# Multi-sensor_Datalogger.net
KiCad netlist of a schematic drawn in Altium Designer
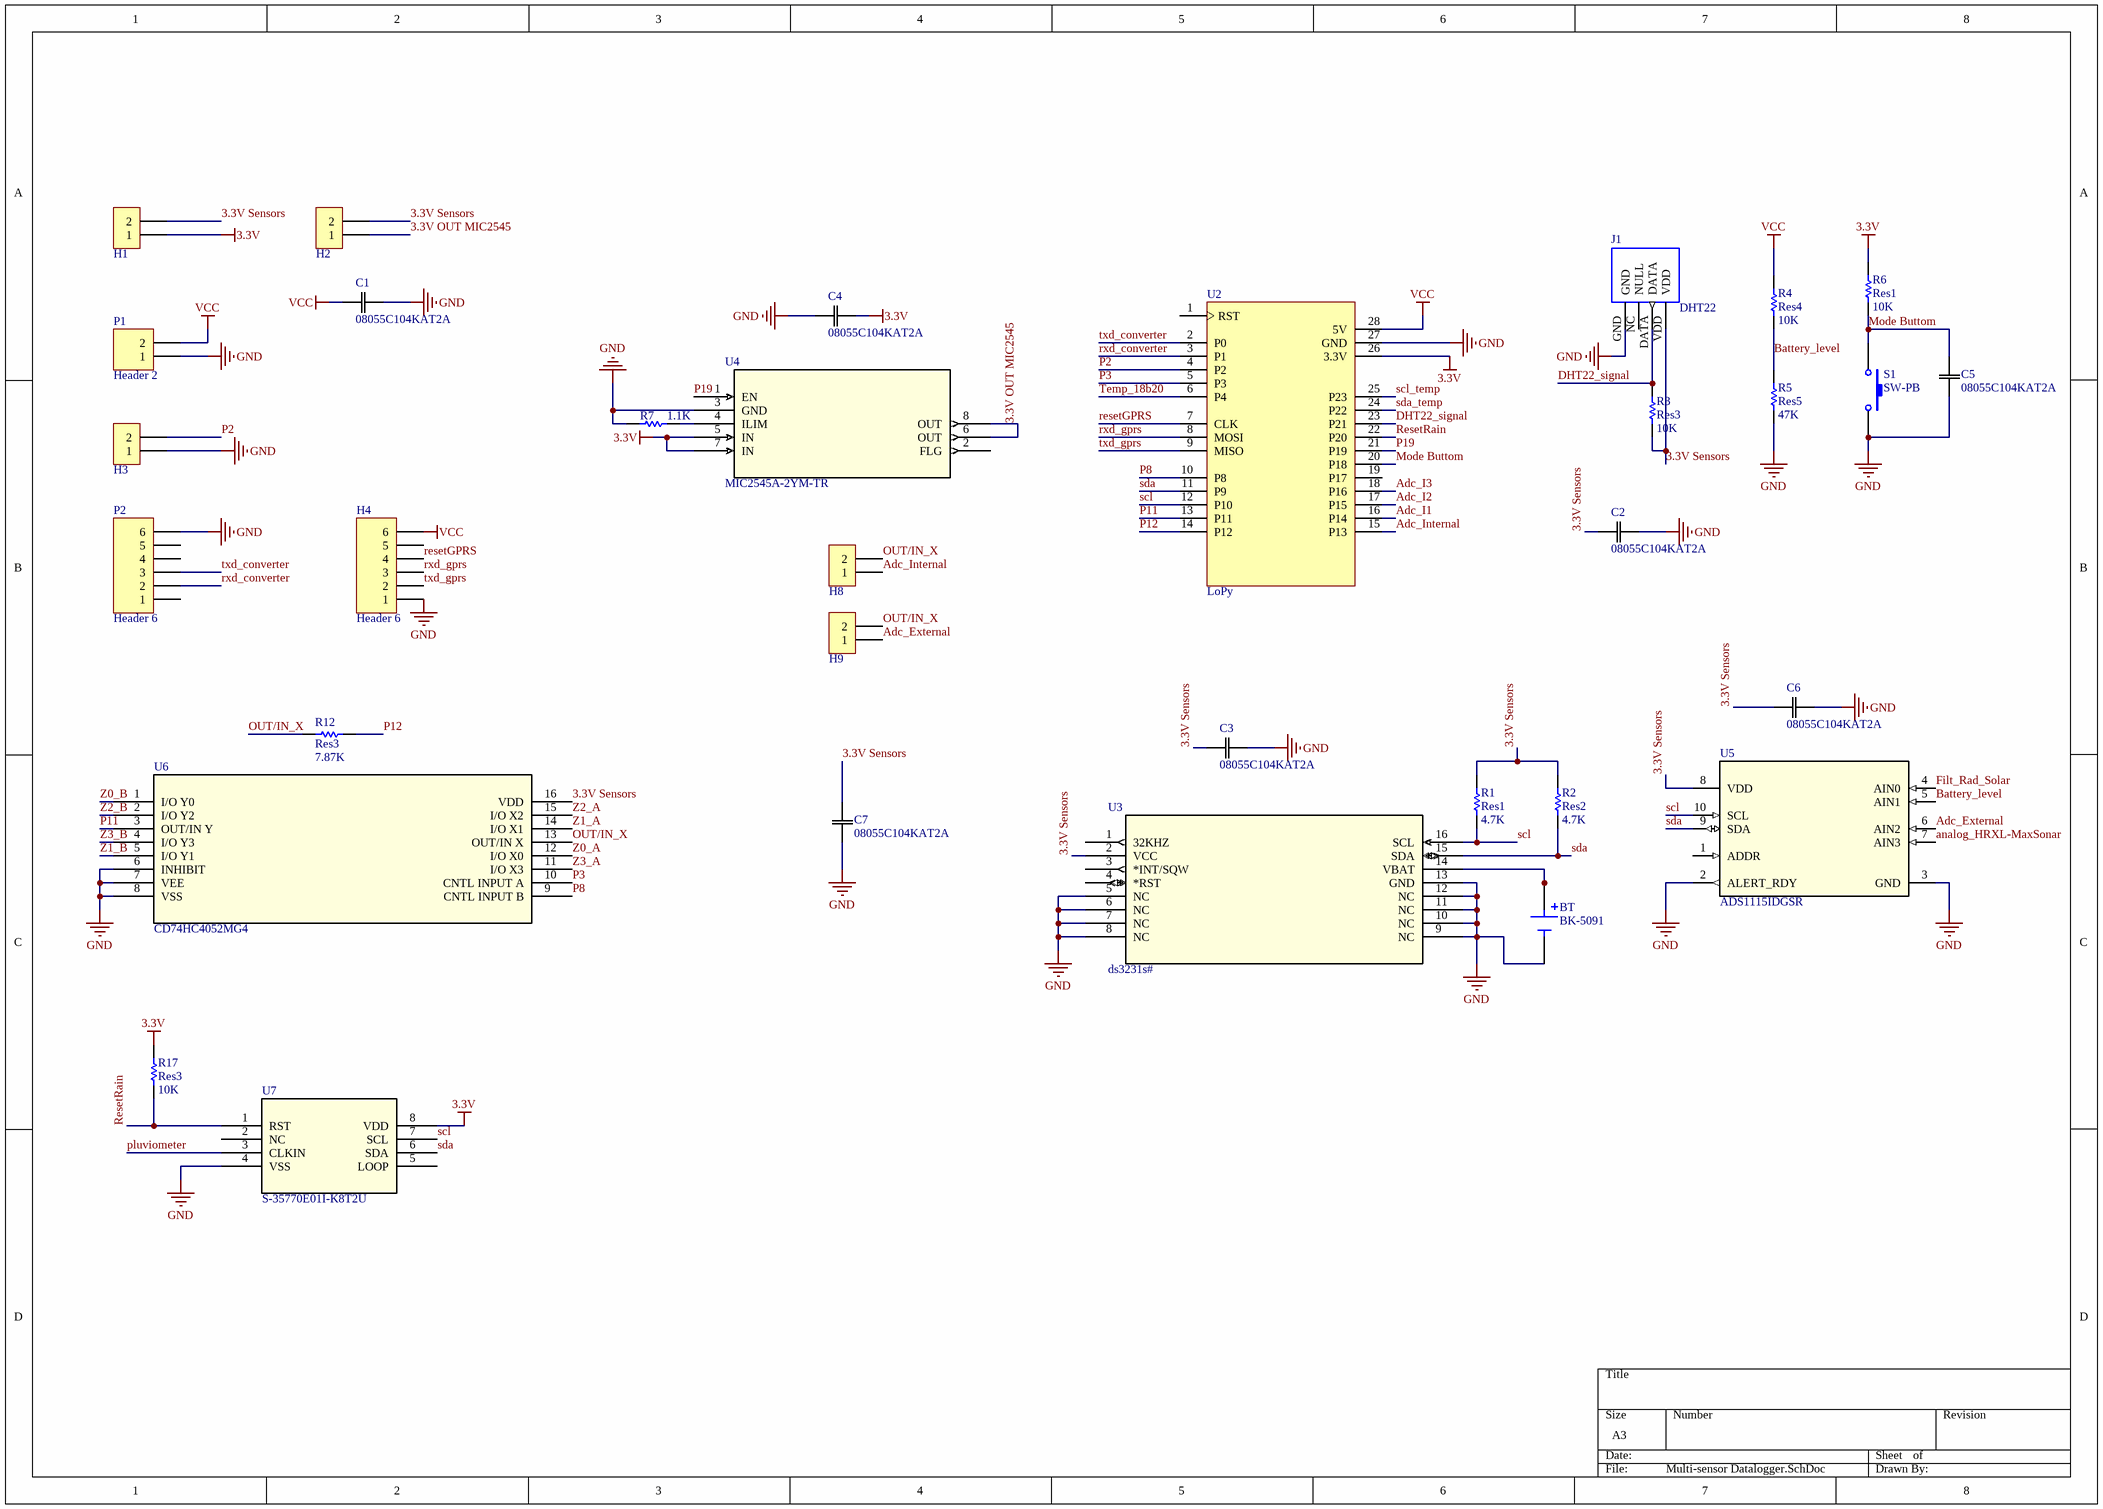
[diagram p0: Multi-sensor Datalogger.SchDoc]

(export (version "E")
  (design (tool "Eeschema 10.0.6"))
  (components
    (comp (ref "BT")
      (value "BK-5091")
      (footprint "SnapEDApcb:BAT_BK-5091")
      (description "Battery Retainer Coin, 11.6mm 1 Cell PC Pin")
      (fields (field (name "MF") "MPD") (field (name "DIGI-KEY_PART_NUMBER") "BK-5091-ND"))
      (libsource (lib "SnapEDAsch") (part "BK-5091"))
    )
    (comp (ref "C1")
      (value "08055C104KAT2A")
      (footprint "CAP_X7R_0805_AVX")
      (description "No Description Available")
      (fields (field (name "COPYRIGHT") "Copyright (C) 2018 Accelerated Designs. All rights reserved"))
      (libsource (lib "cap_0805") (part "08055C104KAT2A"))
    )
    (comp (ref "C2")
      (value "08055C104KAT2A")
      (footprint "CAP_X7R_0805_AVX")
      (description "No Description Available")
      (fields (field (name "COPYRIGHT") "Copyright (C) 2018 Accelerated Designs. All rights reserved"))
      (libsource (lib "cap_0805") (part "08055C104KAT2A"))
    )
    (comp (ref "C3")
      (value "08055C104KAT2A")
      (footprint "CAP_X7R_0805_AVX")
      (description "No Description Available")
      (fields (field (name "COPYRIGHT") "Copyright (C) 2018 Accelerated Designs. All rights reserved"))
      (libsource (lib "cap_0805") (part "08055C104KAT2A"))
    )
    (comp (ref "C4")
      (value "08055C104KAT2A")
      (footprint "CAP_X7R_0805_AVX")
      (description "No Description Available")
      (fields (field (name "COPYRIGHT") "Copyright (C) 2018 Accelerated Designs. All rights reserved"))
      (libsource (lib "cap_0805") (part "08055C104KAT2A"))
    )
    (comp (ref "C5")
      (value "08055C104KAT2A")
      (footprint "CAP_X7R_0805_AVX")
      (description "No Description Available")
      (fields (field (name "COPYRIGHT") "Copyright (C) 2018 Accelerated Designs. All rights reserved"))
      (libsource (lib "cap_0805") (part "08055C104KAT2A"))
    )
    (comp (ref "C6")
      (value "08055C104KAT2A")
      (footprint "CAP_X7R_0805_AVX")
      (description "No Description Available")
      (fields (field (name "COPYRIGHT") "Copyright (C) 2018 Accelerated Designs. All rights reserved"))
      (libsource (lib "cap_0805") (part "08055C104KAT2A"))
    )
    (comp (ref "C7")
      (value "08055C104KAT2A")
      (footprint "CAP_X7R_0805_AVX")
      (description "No Description Available")
      (fields (field (name "COPYRIGHT") "Copyright (C) 2018 Accelerated Designs. All rights reserved"))
      (libsource (lib "cap_0805") (part "08055C104KAT2A"))
    )
    (comp (ref "H1")
      (value "Header")
      (footprint "Header 1X2")
      (description "Header 2 pin")
      (libsource (lib "Conectores") (part "Header 2"))
    )
    (comp (ref "H2")
      (value "Header")
      (footprint "Header 1X2")
      (description "Header 2 pin")
      (libsource (lib "Conectores") (part "Header 2"))
    )
    (comp (ref "H3")
      (value "Header")
      (footprint "Header 1X2")
      (description "Header 2 pin")
      (libsource (lib "Conectores") (part "Header 2"))
    )
    (comp (ref "H4")
      (value "Header 6")
      (footprint "Header 1X6")
      (description "Header, 6-Pin")
      (fields (field (name "PUBLISHER") "Altium Limited"))
      (libsource (lib "Conectores") (part "Header 6"))
    )
    (comp (ref "H8")
      (value "Header")
      (footprint "Header 1X2")
      (description "Header 2 pin")
      (libsource (lib "Conectores") (part "Header 2"))
    )
    (comp (ref "H9")
      (value "Header")
      (footprint "Header 1X2")
      (description "Header 2 pin")
      (libsource (lib "Conectores") (part "Header 2"))
    )
    (comp (ref "J1")
      (value "DHT22")
      (footprint "DHT22:DHT22")
      (description "Capacitive-type humidity and temperature module/sensor")
      (fields (field (name "MF") "Aosong Electronics"))
      (libsource (lib "DHT22") (part "DHT22"))
    )
    (comp (ref "P1")
      (value "Header 2")
      (footprint "BORNERA25-2")
      (description "Header, 2-Pin")
      (fields (field (name "PUBLISHER") "Altium Limited"))
      (libsource (lib "Miscellaneous Connectors_3D") (part "Header 2"))
    )
    (comp (ref "P2")
      (value "Header 6")
      (footprint "HDR1X6")
      (description "Header, 6-Pin")
      (fields (field (name "PUBLISHER") "Altium Limited"))
      (libsource (lib "Miscellaneous Connectors") (part "Header 6"))
    )
    (comp (ref "R1")
      (value "Res1")
      (footprint "6-0805_N")
      (description "Resistor")
      (fields (field (name "ALTIUM_VALUE") "4.7K") (field (name "PUBLISHER") "Altium Limited"))
      (libsource (lib "Miscellaneous Devices") (part "Res1"))
    )
    (comp (ref "R2")
      (value "Res2")
      (footprint "6-0805_N")
      (description "Resistor")
      (fields (field (name "ALTIUM_VALUE") "4.7K") (field (name "PUBLISHER") "Altium Limited"))
      (libsource (lib "Miscellaneous Devices") (part "Res1"))
    )
    (comp (ref "R3")
      (value "Res3")
      (footprint "6-0805_N")
      (description "Resistor")
      (fields (field (name "ALTIUM_VALUE") "10K") (field (name "PUBLISHER") "Altium Limited"))
      (libsource (lib "Miscellaneous Devices") (part "Res1"))
    )
    (comp (ref "R4")
      (value "Res4")
      (footprint "6-0805_N")
      (description "Resistor")
      (fields (field (name "ALTIUM_VALUE") "10K") (field (name "PUBLISHER") "Altium Limited"))
      (libsource (lib "Miscellaneous Devices") (part "Res1"))
    )
    (comp (ref "R5")
      (value "Res5")
      (footprint "6-0805_N")
      (description "Resistor")
      (fields (field (name "ALTIUM_VALUE") "47K") (field (name "PUBLISHER") "Altium Limited"))
      (libsource (lib "Miscellaneous Devices") (part "Res1"))
    )
    (comp (ref "R6")
      (value "Res1")
      (footprint "6-0805_N")
      (description "Resistor")
      (fields (field (name "ALTIUM_VALUE") "10K") (field (name "PUBLISHER") "Altium Limited"))
      (libsource (lib "Miscellaneous Devices") (part "Res1"))
    )
    (comp (ref "R7")
      (value "1.1K")
      (footprint "6-0805_N")
      (description "Resistor")
      (fields (field (name "PUBLISHER") "Altium Limited"))
      (libsource (lib "Miscellaneous Devices") (part "Res1"))
    )
    (comp (ref "R12")
      (value "Res3")
      (footprint "6-0805_N")
      (description "Resistor")
      (fields (field (name "ALTIUM_VALUE") "7.87K") (field (name "PUBLISHER") "Altium Limited"))
      (libsource (lib "Miscellaneous Devices") (part "Res1"))
    )
    (comp (ref "R17")
      (value "Res3")
      (footprint "6-0805_N")
      (description "Resistor")
      (fields (field (name "ALTIUM_VALUE") "10K") (field (name "PUBLISHER") "Altium Limited"))
      (libsource (lib "Miscellaneous Devices") (part "Res1"))
    )
    (comp (ref "S1")
      (value "SW-PB")
      (footprint "BUTTON-1-SMD")
      (description "Switch")
      (fields (field (name "PUBLISHER") "Altium Limited"))
      (libsource (lib "Miscellaneous Devices") (part "SW-PB"))
    )
    (comp (ref "U2")
      (value "LoPy")
      (footprint "LoPy")
      (fields (field (name "PUBLISHER") "Altium Limited"))
      (libsource (lib "LoPy") (part "LoPy"))
    )
    (comp (ref "U3")
      (value "ds3231s#")
      (footprint "21-0042B_16_MXM")
      (description "No Description Available")
      (fields (field (name "COPYRIGHT") "Copyright (C) 2018 Accelerated Designs. All rights reserved"))
      (libsource (lib "2021-01-26_16-05-58") (part "ds3231s#"))
    )
    (comp (ref "U4")
      (value "MIC2545A-2YM-TR")
      (footprint "SOP-8_MCH")
      (description "No Description Available")
      (fields (field (name "COPYRIGHT") "Copyright (C) 2018 Accelerated Designs. All rights reserved"))
      (libsource (lib "MIC2545A-2YM-TR") (part "MIC2545A-2YM-TR"))
    )
    (comp (ref "U5")
      (value "ADS1115IDGSR")
      (footprint "DGS0010A_L")
      (description "No Description Available")
      (fields
        (field (name "MANUFACTURER") "Texas Instruments")
        (field (name "COPYRIGHT") "Copyright (C) 2018 Accelerated Designs. All rights reserved")
      )
      (libsource (lib "ads1115") (part "ADS1115IDGSR"))
    )
    (comp (ref "U6")
      (value "CD74HC4052MG4")
      (footprint "D16_TEX")
      (description "No Description Available")
      (fields (field (name "COPYRIGHT") "Copyright (C) 2021 Accelerated Designs. All rights reserved"))
      (libsource (lib "CD74HC4052smd") (part "CD74HC4052MG4"))
    )
    (comp (ref "U7")
      (value "S-35770E01I-K8T2U")
      (footprint "TMSOP08_2P9X2P8_ABL")
      (description "No Description Available")
      (fields (field (name "COPYRIGHT") "Copyright (C) 2018 Accelerated Designs. All rights reserved"))
      (libsource (lib "S35770") (part "S-35770E01I-K8T2U"))
    )
  )
  (nets
    (net (code "1") (name "/3.3V OUT MIC2545") (class "Default")
      (node (ref "H2") (pin "1") (pinfunction "1_1") (pintype "passive"))
      (node (ref "U4") (pin "6") (pinfunction "OUT_6") (pintype "output"))
      (node (ref "U4") (pin "8") (pinfunction "OUT_8") (pintype "output"))
    )
    (net (code "2") (name "/3.3V Sensors") (class "Default")
      (node (ref "C2") (pin "2") (pinfunction "2_2") (pintype "passive"))
      (node (ref "C3") (pin "2") (pinfunction "2_2") (pintype "passive"))
      (node (ref "C6") (pin "2") (pinfunction "2_2") (pintype "passive"))
      (node (ref "C7") (pin "2") (pinfunction "2_2") (pintype "passive"))
      (node (ref "H1") (pin "2") (pinfunction "2_2") (pintype "passive"))
      (node (ref "H2") (pin "2") (pinfunction "2_2") (pintype "passive"))
      (node (ref "J1") (pin "VDD") (pinfunction "VDD_VDD") (pintype "power_in"))
      (node (ref "R1") (pin "1") (pinfunction "1_1") (pintype "passive"))
      (node (ref "R2") (pin "1") (pinfunction "1_1") (pintype "passive"))
      (node (ref "R3") (pin "2") (pinfunction "2_2") (pintype "passive"))
      (node (ref "U3") (pin "2") (pinfunction "VCC_2") (pintype "power_in"))
      (node (ref "U5") (pin "8") (pinfunction "VDD_8") (pintype "power_in"))
      (node (ref "U6") (pin "16") (pinfunction "VDD_16") (pintype "passive"))
    )
    (net (code "3") (name "/Adc_External") (class "Default")
      (node (ref "H9") (pin "1") (pinfunction "1_1") (pintype "passive"))
      (node (ref "U5") (pin "6") (pinfunction "AIN2_6") (pintype "input"))
    )
    (net (code "4") (name "/Adc_I1") (class "Default")
      (node (ref "U2") (pin "16") (pinfunction "P14_16") (pintype "passive"))
    )
    (net (code "5") (name "/Adc_I2") (class "Default")
      (node (ref "U2") (pin "17") (pinfunction "P15_17") (pintype "passive"))
    )
    (net (code "6") (name "/Adc_I3") (class "Default")
      (node (ref "U2") (pin "18") (pinfunction "P16_18") (pintype "passive"))
    )
    (net (code "7") (name "/Adc_Internal") (class "Default")
      (node (ref "H8") (pin "1") (pinfunction "1_1") (pintype "passive"))
      (node (ref "U2") (pin "15") (pinfunction "P13_15") (pintype "passive"))
    )
    (net (code "8") (name "/Battery_level") (class "Default")
      (node (ref "R4") (pin "2") (pinfunction "2_2") (pintype "passive"))
      (node (ref "R5") (pin "1") (pinfunction "1_1") (pintype "passive"))
      (node (ref "U5") (pin "5") (pinfunction "AIN1_5") (pintype "input"))
    )
    (net (code "9") (name "/DHT22_signal") (class "Default")
      (node (ref "J1") (pin "DATA") (pinfunction "DATA_DATA") (pintype "output"))
      (node (ref "R3") (pin "1") (pinfunction "1_1") (pintype "passive"))
      (node (ref "U2") (pin "23") (pinfunction "P21_23") (pintype "passive"))
    )
    (net (code "10") (name "/Filt_Rad_Solar") (class "Default")
      (node (ref "U5") (pin "4") (pinfunction "AIN0_4") (pintype "input"))
    )
    (net (code "11") (name "/Mode Buttom") (class "Default")
      (node (ref "C5") (pin "2") (pinfunction "2_2") (pintype "passive"))
      (node (ref "R6") (pin "2") (pinfunction "2_2") (pintype "passive"))
      (node (ref "S1") (pin "1") (pinfunction "1_1") (pintype "passive"))
      (node (ref "U2") (pin "20") (pinfunction "P18_20") (pintype "passive"))
    )
    (net (code "12") (name "/OUT{slash}IN_X") (class "Default")
      (node (ref "H8") (pin "2") (pinfunction "2_2") (pintype "passive"))
      (node (ref "H9") (pin "2") (pinfunction "2_2") (pintype "passive"))
      (node (ref "R12") (pin "1") (pinfunction "1_1") (pintype "passive"))
      (node (ref "U6") (pin "13") (pinfunction "OUT/IN_X_13") (pintype "passive"))
    )
    (net (code "13") (name "/P2") (class "Default")
      (node (ref "H3") (pin "2") (pinfunction "2_2") (pintype "passive"))
      (node (ref "U2") (pin "4") (pinfunction "P2_4") (pintype "passive"))
    )
    (net (code "14") (name "/P3") (class "Default")
      (node (ref "U2") (pin "5") (pinfunction "P3_5") (pintype "passive"))
      (node (ref "U6") (pin "10") (pinfunction "CNTL_INPUT_A_10") (pintype "passive"))
    )
    (net (code "15") (name "/P8") (class "Default")
      (node (ref "U2") (pin "10") (pinfunction "P8_10") (pintype "passive"))
      (node (ref "U6") (pin "9") (pinfunction "CNTL_INPUT_B_9") (pintype "passive"))
    )
    (net (code "16") (name "/P11") (class "Default")
      (node (ref "U2") (pin "13") (pinfunction "P11_13") (pintype "passive"))
      (node (ref "U6") (pin "3") (pinfunction "OUT/IN_Y_3") (pintype "passive"))
    )
    (net (code "17") (name "/P12") (class "Default")
      (node (ref "R12") (pin "2") (pinfunction "2_2") (pintype "passive"))
      (node (ref "U2") (pin "14") (pinfunction "P12_14") (pintype "passive"))
    )
    (net (code "18") (name "/P19") (class "Default")
      (node (ref "U2") (pin "21") (pinfunction "P19_21") (pintype "passive"))
      (node (ref "U4") (pin "1") (pinfunction "EN_1") (pintype "input"))
    )
    (net (code "19") (name "/ResetRain") (class "Default")
      (node (ref "R17") (pin "2") (pinfunction "2_2") (pintype "passive"))
      (node (ref "U2") (pin "22") (pinfunction "P20_22") (pintype "passive"))
      (node (ref "U7") (pin "1") (pinfunction "RST_1") (pintype "passive"))
    )
    (net (code "20") (name "/Temp_18b20") (class "Default")
      (node (ref "U2") (pin "6") (pinfunction "P4_6") (pintype "passive"))
    )
    (net (code "21") (name "/Z0_A") (class "Default")
      (node (ref "U6") (pin "12") (pinfunction "I/O_X0_12") (pintype "passive"))
    )
    (net (code "22") (name "/Z0_B") (class "Default")
      (node (ref "U6") (pin "1") (pinfunction "I/O_Y0_1") (pintype "passive"))
    )
    (net (code "23") (name "/Z1_A") (class "Default")
      (node (ref "U6") (pin "14") (pinfunction "I/O_X1_14") (pintype "passive"))
    )
    (net (code "24") (name "/Z1_B") (class "Default")
      (node (ref "U6") (pin "5") (pinfunction "I/O_Y1_5") (pintype "passive"))
    )
    (net (code "25") (name "/Z2_A") (class "Default")
      (node (ref "U6") (pin "15") (pinfunction "I/O_X2_15") (pintype "passive"))
    )
    (net (code "26") (name "/Z2_B") (class "Default")
      (node (ref "U6") (pin "2") (pinfunction "I/O_Y2_2") (pintype "passive"))
    )
    (net (code "27") (name "/Z3_A") (class "Default")
      (node (ref "U6") (pin "11") (pinfunction "I/O_X3_11") (pintype "passive"))
    )
    (net (code "28") (name "/Z3_B") (class "Default")
      (node (ref "U6") (pin "4") (pinfunction "I/O_Y3_4") (pintype "passive"))
    )
    (net (code "29") (name "/analog_HRXL-MaxSonar") (class "Default")
      (node (ref "U5") (pin "7") (pinfunction "AIN3_7") (pintype "input"))
    )
    (net (code "30") (name "/pluviometer") (class "Default")
      (node (ref "U7") (pin "3") (pinfunction "CLKIN_3") (pintype "passive"))
    )
    (net (code "31") (name "/resetGPRS") (class "Default")
      (node (ref "H4") (pin "4") (pinfunction "4_4") (pintype "passive"))
      (node (ref "U2") (pin "7") (pinfunction "CLK_7") (pintype "passive"))
    )
    (net (code "32") (name "/rxd_converter") (class "Default")
      (node (ref "P2") (pin "2") (pinfunction "2_2") (pintype "passive"))
      (node (ref "U2") (pin "3") (pinfunction "P1_3") (pintype "passive"))
    )
    (net (code "33") (name "/rxd_gprs") (class "Default")
      (node (ref "H4") (pin "3") (pinfunction "3_3") (pintype "passive"))
      (node (ref "U2") (pin "8") (pinfunction "MOSI_8") (pintype "passive"))
    )
    (net (code "34") (name "/scl") (class "Default")
      (node (ref "R1") (pin "2") (pinfunction "2_2") (pintype "passive"))
      (node (ref "U2") (pin "12") (pinfunction "P10_12") (pintype "passive"))
      (node (ref "U3") (pin "16") (pinfunction "SCL_16") (pintype "input"))
      (node (ref "U5") (pin "10") (pinfunction "SCL_10") (pintype "input"))
      (node (ref "U7") (pin "7") (pinfunction "SCL_7") (pintype "passive"))
    )
    (net (code "35") (name "/scl_temp") (class "Default")
      (node (ref "U2") (pin "25") (pinfunction "P23_25") (pintype "passive"))
    )
    (net (code "36") (name "/sda") (class "Default")
      (node (ref "R2") (pin "2") (pinfunction "2_2") (pintype "passive"))
      (node (ref "U2") (pin "11") (pinfunction "P9_11") (pintype "passive"))
      (node (ref "U3") (pin "15") (pinfunction "SDA_15") (pintype "bidirectional"))
      (node (ref "U5") (pin "9") (pinfunction "SDA_9") (pintype "bidirectional"))
      (node (ref "U7") (pin "6") (pinfunction "SDA_6") (pintype "passive"))
    )
    (net (code "37") (name "/sda_temp") (class "Default")
      (node (ref "U2") (pin "24") (pinfunction "P22_24") (pintype "passive"))
    )
    (net (code "38") (name "/txd_converter") (class "Default")
      (node (ref "P2") (pin "3") (pinfunction "3_3") (pintype "passive"))
      (node (ref "U2") (pin "2") (pinfunction "P0_2") (pintype "power_in"))
    )
    (net (code "39") (name "/txd_gprs") (class "Default")
      (node (ref "H4") (pin "2") (pinfunction "2_2") (pintype "passive"))
      (node (ref "U2") (pin "9") (pinfunction "MISO_9") (pintype "passive"))
    )
    (net (code "40") (name "3.3V") (class "Default")
      (node (ref "C4") (pin "1") (pinfunction "1_1") (pintype "passive"))
      (node (ref "H1") (pin "1") (pinfunction "1_1") (pintype "passive"))
      (node (ref "R17") (pin "1") (pinfunction "1_1") (pintype "passive"))
      (node (ref "R6") (pin "1") (pinfunction "1_1") (pintype "passive"))
      (node (ref "U2") (pin "26") (pinfunction "3.3V_26") (pintype "passive"))
      (node (ref "U4") (pin "5") (pinfunction "IN_5") (pintype "input"))
      (node (ref "U4") (pin "7") (pinfunction "IN_7") (pintype "input"))
      (node (ref "U7") (pin "8") (pinfunction "VDD_8") (pintype "power_in"))
    )
    (net (code "41") (name "GND") (class "Default")
      (node (ref "BT") (pin "NEG") (pinfunction "NEG_NEG") (pintype "passive"))
      (node (ref "C1") (pin "1") (pinfunction "1_1") (pintype "passive"))
      (node (ref "C2") (pin "1") (pinfunction "1_1") (pintype "passive"))
      (node (ref "C3") (pin "1") (pinfunction "1_1") (pintype "passive"))
      (node (ref "C4") (pin "2") (pinfunction "2_2") (pintype "passive"))
      (node (ref "C5") (pin "1") (pinfunction "1_1") (pintype "passive"))
      (node (ref "C6") (pin "1") (pinfunction "1_1") (pintype "passive"))
      (node (ref "C7") (pin "1") (pinfunction "1_1") (pintype "passive"))
      (node (ref "H3") (pin "1") (pinfunction "1_1") (pintype "passive"))
      (node (ref "H4") (pin "1") (pinfunction "1_1") (pintype "passive"))
      (node (ref "J1") (pin "GND") (pinfunction "GND_GND") (pintype "power_in"))
      (node (ref "P1") (pin "1") (pinfunction "1_1") (pintype "passive"))
      (node (ref "P2") (pin "6") (pinfunction "6_6") (pintype "passive"))
      (node (ref "R5") (pin "2") (pinfunction "2_2") (pintype "passive"))
      (node (ref "R7") (pin "1") (pinfunction "1_1") (pintype "passive"))
      (node (ref "S1") (pin "2") (pinfunction "2_2") (pintype "passive"))
      (node (ref "U2") (pin "27") (pinfunction "GND_27") (pintype "passive"))
      (node (ref "U3") (pin "10") (pinfunction "NC_10") (pintype "passive"))
      (node (ref "U3") (pin "11") (pinfunction "NC_11") (pintype "passive"))
      (node (ref "U3") (pin "12") (pinfunction "NC_12") (pintype "passive"))
      (node (ref "U3") (pin "13") (pinfunction "GND_13") (pintype "power_in"))
      (node (ref "U3") (pin "5") (pinfunction "NC_5") (pintype "passive"))
      (node (ref "U3") (pin "6") (pinfunction "NC_6") (pintype "passive"))
      (node (ref "U3") (pin "7") (pinfunction "NC_7") (pintype "passive"))
      (node (ref "U3") (pin "8") (pinfunction "NC_8") (pintype "passive"))
      (node (ref "U3") (pin "9") (pinfunction "NC_9") (pintype "passive"))
      (node (ref "U4") (pin "3") (pinfunction "GND_3") (pintype "power_in"))
      (node (ref "U5") (pin "2") (pinfunction "ALERT_RDY_2") (pintype "output"))
      (node (ref "U5") (pin "3") (pinfunction "GND_3") (pintype "power_in"))
      (node (ref "U6") (pin "6") (pinfunction "INHIBIT_6") (pintype "passive"))
      (node (ref "U6") (pin "7") (pinfunction "VEE_7") (pintype "passive"))
      (node (ref "U6") (pin "8") (pinfunction "VSS_8") (pintype "passive"))
      (node (ref "U7") (pin "4") (pinfunction "VSS_4") (pintype "passive"))
    )
    (net (code "42") (name "Net-(U3-VBAT)") (class "Default")
      (node (ref "BT") (pin "1+") (pinfunction "POS_1+") (pintype "passive"))
      (node (ref "BT") (pin "2+") (pinfunction "POS_2+") (pintype "passive"))
      (node (ref "U3") (pin "14") (pinfunction "VBAT_14") (pintype "power_in"))
    )
    (net (code "43") (name "Net-(U4-ILIM)") (class "Default")
      (node (ref "R7") (pin "2") (pinfunction "2_2") (pintype "passive"))
      (node (ref "U4") (pin "4") (pinfunction "ILIM_4") (pintype "passive"))
    )
    (net (code "44") (name "VCC") (class "Default")
      (node (ref "C1") (pin "2") (pinfunction "2_2") (pintype "passive"))
      (node (ref "H4") (pin "6") (pinfunction "6_6") (pintype "passive"))
      (node (ref "P1") (pin "2") (pinfunction "2_2") (pintype "passive"))
      (node (ref "R4") (pin "1") (pinfunction "1_1") (pintype "passive"))
      (node (ref "U2") (pin "28") (pinfunction "5V_28") (pintype "passive"))
    )
    (net (code "45") (name "unconnected-(H4-Pad5)") (class "Default")
      (node (ref "H4") (pin "5") (pinfunction "5_5") (pintype "passive"))
    )
    (net (code "46") (name "unconnected-(J1-NULL-PadNC)") (class "Default")
      (node (ref "J1") (pin "NC") (pinfunction "NULL_NC") (pintype "passive"))
    )
    (net (code "47") (name "unconnected-(P2-Pad1)") (class "Default")
      (node (ref "P2") (pin "1") (pinfunction "1_1") (pintype "passive"))
    )
    (net (code "48") (name "unconnected-(P2-Pad4)") (class "Default")
      (node (ref "P2") (pin "4") (pinfunction "4_4") (pintype "passive"))
    )
    (net (code "49") (name "unconnected-(P2-Pad5)") (class "Default")
      (node (ref "P2") (pin "5") (pinfunction "5_5") (pintype "passive"))
    )
    (net (code "50") (name "unconnected-(U2-P17-Pad19)") (class "Default")
      (node (ref "U2") (pin "19") (pinfunction "P17_19") (pintype "passive"))
    )
    (net (code "51") (name "unconnected-(U2-RST-Pad1)") (class "Default")
      (node (ref "U2") (pin "1") (pinfunction "RST_1") (pintype "passive"))
    )
    (net (code "52") (name "unconnected-(U3-*INT{slash}SQW-Pad3)") (class "Default")
      (node (ref "U3") (pin "3") (pinfunction "*INT/SQW_3") (pintype "output"))
    )
    (net (code "53") (name "unconnected-(U3-*RST-Pad4)") (class "Default")
      (node (ref "U3") (pin "4") (pinfunction "*RST_4") (pintype "bidirectional"))
    )
    (net (code "54") (name "unconnected-(U3-32KHZ-Pad1)") (class "Default")
      (node (ref "U3") (pin "1") (pinfunction "32KHZ_1") (pintype "output"))
    )
    (net (code "55") (name "unconnected-(U4-FLG-Pad2)") (class "Default")
      (node (ref "U4") (pin "2") (pinfunction "FLG_2") (pintype "output"))
    )
    (net (code "56") (name "unconnected-(U5-ADDR-Pad1)") (class "Default")
      (node (ref "U5") (pin "1") (pinfunction "ADDR_1") (pintype "input"))
    )
    (net (code "57") (name "unconnected-(U7-LOOP-Pad5)") (class "Default")
      (node (ref "U7") (pin "5") (pinfunction "LOOP_5") (pintype "passive"))
    )
    (net (code "58") (name "unconnected-(U7-NC-Pad2)") (class "Default")
      (node (ref "U7") (pin "2") (pinfunction "NC_2") (pintype "passive"))
    )
  )
)
